# muster_1.net
KiCad netlist of a schematic drawn in EAGLE
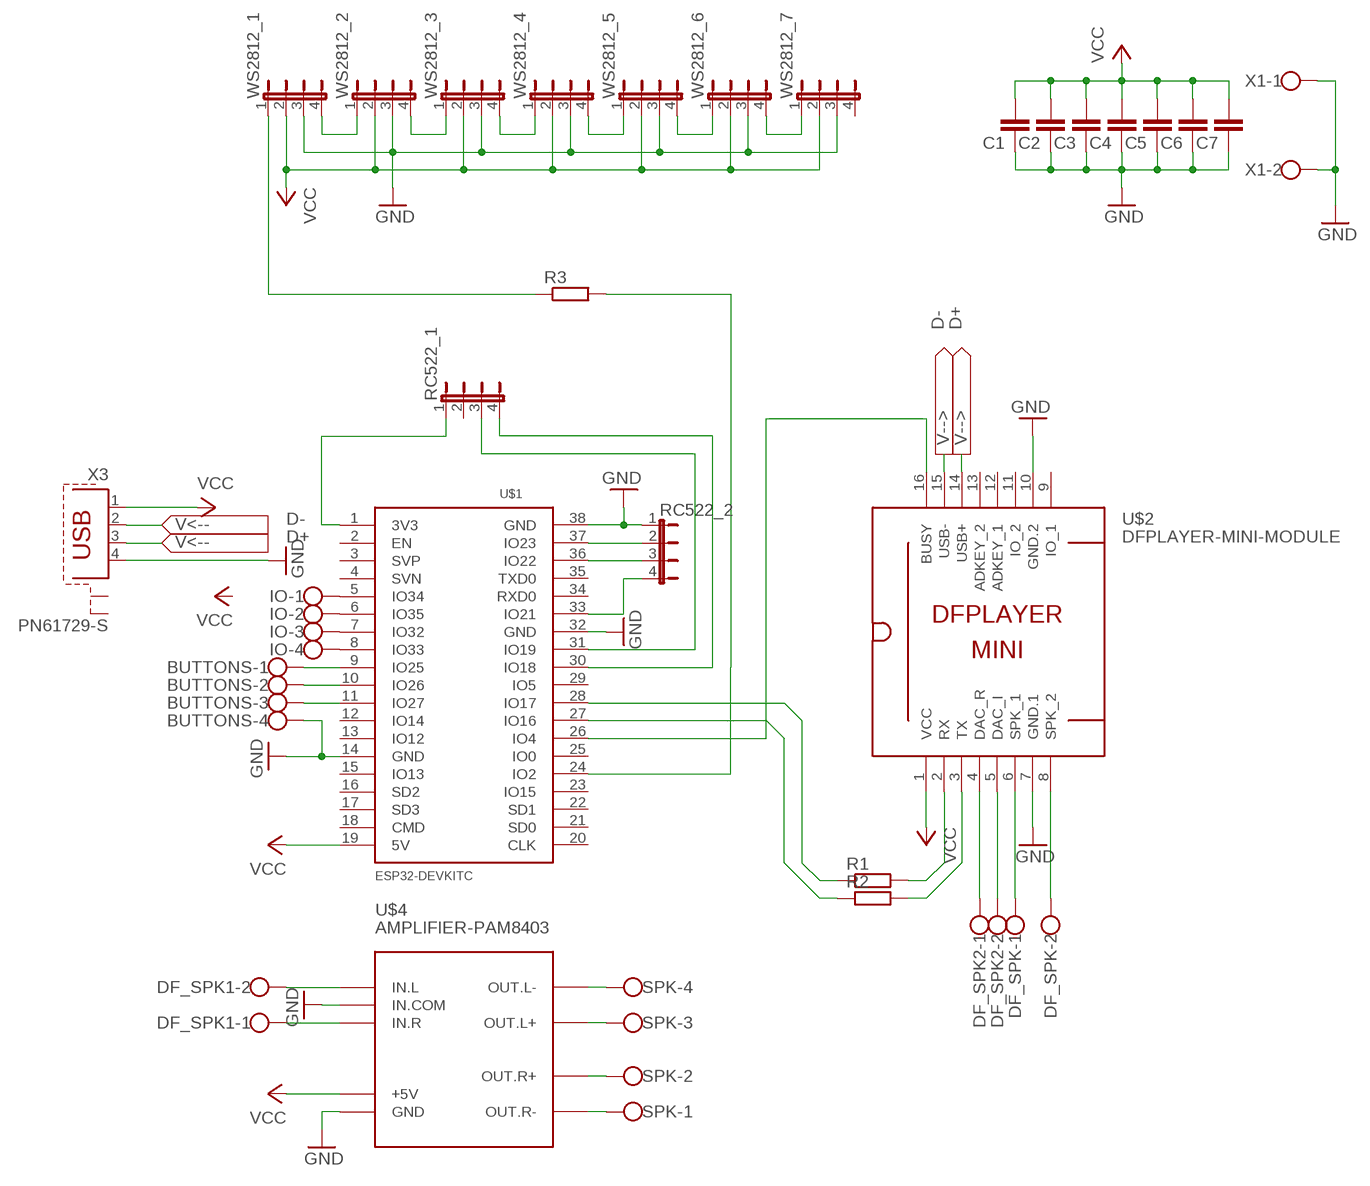
[diagram p0: schematic, sheet 1]

(export (version "E")
  (design (tool "Eeschema 10.0.6"))
  (components
    (comp (ref "BUTTONS")
      (value "W237-4")
      (footprint "eagle-import:W237-4")
      (libsource (lib "eagle-import") (part "W237-4"))
    )
    (comp (ref "C1")
      (value "C-EU025-024X044")
      (footprint "eagle-import:C025-024X044")
      (libsource (lib "eagle-import") (part "C-EU025-024X044"))
    )
    (comp (ref "C2")
      (value "C-EU025-025X050")
      (footprint "eagle-import:C025-025X050")
      (libsource (lib "eagle-import") (part "C-EU025-025X050"))
    )
    (comp (ref "C3")
      (value "C-EU025-025X050")
      (footprint "eagle-import:C025-025X050")
      (libsource (lib "eagle-import") (part "C-EU025-025X050"))
    )
    (comp (ref "C4")
      (value "C-EU025-025X050")
      (footprint "eagle-import:C025-025X050")
      (libsource (lib "eagle-import") (part "C-EU025-025X050"))
    )
    (comp (ref "C5")
      (value "C-EU025-025X050")
      (footprint "eagle-import:C025-025X050")
      (libsource (lib "eagle-import") (part "C-EU025-025X050"))
    )
    (comp (ref "C6")
      (value "C-EU025-025X050")
      (footprint "eagle-import:C025-025X050")
      (libsource (lib "eagle-import") (part "C-EU025-025X050"))
    )
    (comp (ref "C7")
      (value "C-EU025-025X050")
      (footprint "eagle-import:C025-025X050")
      (libsource (lib "eagle-import") (part "C-EU025-025X050"))
    )
    (comp (ref "DF_SPK")
      (value "W237-02P")
      (footprint "eagle-import:W237-132")
      (libsource (lib "eagle-import") (part "W237-02P"))
    )
    (comp (ref "DF_SPK1")
      (value "W237-02P")
      (footprint "eagle-import:W237-132")
      (libsource (lib "eagle-import") (part "W237-02P"))
    )
    (comp (ref "DF_SPK2")
      (value "W237-02P")
      (footprint "eagle-import:W237-132")
      (libsource (lib "eagle-import") (part "W237-02P"))
    )
    (comp (ref "IO")
      (value "W237-4")
      (footprint "eagle-import:W237-4")
      (libsource (lib "eagle-import") (part "W237-4"))
    )
    (comp (ref "R1")
      (value "R-EU_0204/2V")
      (footprint "eagle-import:0204V")
      (libsource (lib "eagle-import") (part "R-EU_0204/2V"))
    )
    (comp (ref "R2")
      (value "R-EU_0204/2V")
      (footprint "eagle-import:0204V")
      (libsource (lib "eagle-import") (part "R-EU_0204/2V"))
    )
    (comp (ref "R3")
      (value "R-EU_0204/2V")
      (footprint "eagle-import:0204V")
      (libsource (lib "eagle-import") (part "R-EU_0204/2V"))
    )
    (comp (ref "RC522_1")
      (value "JP4E")
      (footprint "eagle-import:JP4")
      (libsource (lib "eagle-import") (part "JP4E"))
    )
    (comp (ref "RC522_2")
      (value "JP4E")
      (footprint "eagle-import:JP4")
      (libsource (lib "eagle-import") (part "JP4E"))
    )
    (comp (ref "SPK")
      (value "W237-4")
      (footprint "eagle-import:W237-4")
      (libsource (lib "eagle-import") (part "W237-4"))
    )
    (comp (ref "U$1")
      (value "ESP32DEVKITC")
      (footprint "eagle-import:ESP32-DEVKITC")
      (libsource (lib "eagle-import") (part "ESP32DEVKITC"))
    )
    (comp (ref "U$2")
      (value "DFPLAYER-MINI-MODULE")
      (footprint "eagle-import:DFPLAYER-MINI-MODULE")
      (libsource (lib "eagle-import") (part "DFPLAYER-MINI-MODULE"))
    )
    (comp (ref "U$4")
      (value "AMPLIFIER-PAM8403")
      (footprint "eagle-import:AMPLIFIER-PAM8403")
      (libsource (lib "eagle-import") (part "AMPLIFIER-PAM8403"))
    )
    (comp (ref "WS2812_1")
      (value "JP4E")
      (footprint "eagle-import:JP4")
      (libsource (lib "eagle-import") (part "JP4E"))
    )
    (comp (ref "WS2812_2")
      (value "JP4E")
      (footprint "eagle-import:JP4")
      (libsource (lib "eagle-import") (part "JP4E"))
    )
    (comp (ref "WS2812_3")
      (value "JP4E")
      (footprint "eagle-import:JP4")
      (libsource (lib "eagle-import") (part "JP4E"))
    )
    (comp (ref "WS2812_4")
      (value "JP4E")
      (footprint "eagle-import:JP4")
      (libsource (lib "eagle-import") (part "JP4E"))
    )
    (comp (ref "WS2812_5")
      (value "JP4E")
      (footprint "eagle-import:JP4")
      (libsource (lib "eagle-import") (part "JP4E"))
    )
    (comp (ref "WS2812_6")
      (value "JP4E")
      (footprint "eagle-import:JP4")
      (libsource (lib "eagle-import") (part "JP4E"))
    )
    (comp (ref "WS2812_7")
      (value "JP4E")
      (footprint "eagle-import:JP4")
      (libsource (lib "eagle-import") (part "JP4E"))
    )
    (comp (ref "X1")
      (value "W237-102")
      (footprint "eagle-import:W237-102")
      (libsource (lib "eagle-import") (part "W237-102"))
    )
    (comp (ref "X3")
      (value "PN61729-S")
      (footprint "eagle-import:PN61729-S")
      (libsource (lib "eagle-import") (part "PN61729-S"))
    )
  )
  (nets
    (net (code "1") (name "/D+") (class "Default")
      (node (ref "U$2") (pin "14") (pinfunction "USB+_14") (pintype "bidirectional"))
      (node (ref "X3") (pin "3") (pinfunction "3_3") (pintype "passive"))
    )
    (net (code "2") (name "/D-") (class "Default")
      (node (ref "U$2") (pin "15") (pinfunction "USB-_15") (pintype "bidirectional"))
      (node (ref "X3") (pin "2") (pinfunction "2_2") (pintype "passive"))
    )
    (net (code "3") (name "GND") (class "Default")
      (node (ref "BUTTONS") (pin "4") (pinfunction "KL_4") (pintype "passive"))
      (node (ref "C1") (pin "1") (pinfunction "1_1") (pintype "passive"))
      (node (ref "C2") (pin "1") (pinfunction "1_1") (pintype "passive"))
      (node (ref "C3") (pin "1") (pinfunction "1_1") (pintype "passive"))
      (node (ref "C4") (pin "1") (pinfunction "1_1") (pintype "passive"))
      (node (ref "C5") (pin "1") (pinfunction "1_1") (pintype "passive"))
      (node (ref "C6") (pin "1") (pinfunction "1_1") (pintype "passive"))
      (node (ref "C7") (pin "1") (pinfunction "1_1") (pintype "passive"))
      (node (ref "RC522_2") (pin "1") (pinfunction "1_1") (pintype "passive"))
      (node (ref "U$1") (pin "14") (pinfunction "GND_14") (pintype "bidirectional"))
      (node (ref "U$1") (pin "32") (pinfunction "GND_32") (pintype "bidirectional"))
      (node (ref "U$1") (pin "38") (pinfunction "GND_38") (pintype "bidirectional"))
      (node (ref "U$2") (pin "10") (pinfunction "GND.2_10") (pintype "power_in"))
      (node (ref "U$2") (pin "7") (pinfunction "GND.1_7") (pintype "power_in"))
      (node (ref "U$4") (pin "GND") (pinfunction "GND_GND") (pintype "power_in"))
      (node (ref "U$4") (pin "IN.COM") (pinfunction "IN.COM_IN.COM") (pintype "input"))
      (node (ref "WS2812_1") (pin "3") (pinfunction "3_3") (pintype "passive"))
      (node (ref "WS2812_2") (pin "3") (pinfunction "3_3") (pintype "passive"))
      (node (ref "WS2812_3") (pin "3") (pinfunction "3_3") (pintype "passive"))
      (node (ref "WS2812_4") (pin "3") (pinfunction "3_3") (pintype "passive"))
      (node (ref "WS2812_5") (pin "3") (pinfunction "3_3") (pintype "passive"))
      (node (ref "WS2812_6") (pin "3") (pinfunction "3_3") (pintype "passive"))
      (node (ref "WS2812_7") (pin "3") (pinfunction "3_3") (pintype "passive"))
      (node (ref "X1") (pin "1") (pinfunction "KL_1") (pintype "passive"))
      (node (ref "X1") (pin "2") (pinfunction "KL_2") (pintype "passive"))
      (node (ref "X3") (pin "4") (pinfunction "4_4") (pintype "passive"))
    )
    (net (code "4") (name "Net-(BUTTONSA-KL)") (class "Default")
      (node (ref "BUTTONS") (pin "1") (pinfunction "KL_1") (pintype "passive"))
      (node (ref "U$1") (pin "9") (pinfunction "IO25_9") (pintype "bidirectional"))
    )
    (net (code "5") (name "Net-(BUTTONSB-KL)") (class "Default")
      (node (ref "BUTTONS") (pin "2") (pinfunction "KL_2") (pintype "passive"))
      (node (ref "U$1") (pin "10") (pinfunction "IO26_10") (pintype "bidirectional"))
    )
    (net (code "6") (name "Net-(BUTTONSC-KL)") (class "Default")
      (node (ref "BUTTONS") (pin "3") (pinfunction "KL_3") (pintype "passive"))
      (node (ref "U$1") (pin "11") (pinfunction "IO27_11") (pintype "bidirectional"))
    )
    (net (code "7") (name "Net-(DF_SPK1A-KL)") (class "Default")
      (node (ref "DF_SPK1") (pin "1") (pinfunction "KL_1") (pintype "passive"))
      (node (ref "U$4") (pin "IN.R") (pinfunction "IN.R_IN.R") (pintype "bidirectional"))
    )
    (net (code "8") (name "Net-(DF_SPK1B-KL)") (class "Default")
      (node (ref "DF_SPK1") (pin "2") (pinfunction "KL_2") (pintype "passive"))
      (node (ref "U$4") (pin "IN.L") (pinfunction "IN.L_IN.L") (pintype "input"))
    )
    (net (code "9") (name "Net-(DF_SPK2A-KL)") (class "Default")
      (node (ref "DF_SPK2") (pin "1") (pinfunction "KL_1") (pintype "passive"))
      (node (ref "U$2") (pin "4") (pinfunction "DAC_R_4") (pintype "bidirectional"))
    )
    (net (code "10") (name "Net-(DF_SPK2B-KL)") (class "Default")
      (node (ref "DF_SPK2") (pin "2") (pinfunction "KL_2") (pintype "passive"))
      (node (ref "U$2") (pin "5") (pinfunction "DAC_I_5") (pintype "bidirectional"))
    )
    (net (code "11") (name "Net-(DF_SPKA-KL)") (class "Default")
      (node (ref "DF_SPK") (pin "1") (pinfunction "KL_1") (pintype "passive"))
      (node (ref "U$2") (pin "6") (pinfunction "SPK_1_6") (pintype "bidirectional"))
    )
    (net (code "12") (name "Net-(DF_SPKB-KL)") (class "Default")
      (node (ref "DF_SPK") (pin "2") (pinfunction "KL_2") (pintype "passive"))
      (node (ref "U$2") (pin "8") (pinfunction "SPK_2_8") (pintype "bidirectional"))
    )
    (net (code "13") (name "Net-(IOA-KL)") (class "Default")
      (node (ref "IO") (pin "1") (pinfunction "KL_1") (pintype "passive"))
      (node (ref "U$1") (pin "5") (pinfunction "IO34_5") (pintype "bidirectional"))
    )
    (net (code "14") (name "Net-(IOB-KL)") (class "Default")
      (node (ref "IO") (pin "2") (pinfunction "KL_2") (pintype "passive"))
      (node (ref "U$1") (pin "6") (pinfunction "IO35_6") (pintype "bidirectional"))
    )
    (net (code "15") (name "Net-(IOC-KL)") (class "Default")
      (node (ref "IO") (pin "3") (pinfunction "KL_3") (pintype "passive"))
      (node (ref "U$1") (pin "7") (pinfunction "IO32_7") (pintype "bidirectional"))
    )
    (net (code "16") (name "Net-(IOD-KL)") (class "Default")
      (node (ref "IO") (pin "4") (pinfunction "KL_4") (pintype "passive"))
      (node (ref "U$1") (pin "8") (pinfunction "IO33_8") (pintype "bidirectional"))
    )
    (net (code "17") (name "Net-(R3-Pad1)") (class "Default")
      (node (ref "R3") (pin "1") (pinfunction "1_1") (pintype "passive"))
      (node (ref "WS2812_1") (pin "1") (pinfunction "1_1") (pintype "passive"))
    )
    (net (code "18") (name "Net-(SPKA-KL)") (class "Default")
      (node (ref "SPK") (pin "1") (pinfunction "KL_1") (pintype "passive"))
      (node (ref "U$4") (pin "OUT.R-") (pinfunction "OUT.R-_OUT.R-") (pintype "output"))
    )
    (net (code "19") (name "Net-(SPKB-KL)") (class "Default")
      (node (ref "SPK") (pin "2") (pinfunction "KL_2") (pintype "passive"))
      (node (ref "U$4") (pin "OUT.R+") (pinfunction "OUT.R+_OUT.R+") (pintype "output"))
    )
    (net (code "20") (name "Net-(SPKC-KL)") (class "Default")
      (node (ref "SPK") (pin "3") (pinfunction "KL_3") (pintype "passive"))
      (node (ref "U$4") (pin "OUT.L+") (pinfunction "OUT.L+_OUT.L+") (pintype "output"))
    )
    (net (code "21") (name "Net-(SPKD-KL)") (class "Default")
      (node (ref "SPK") (pin "4") (pinfunction "KL_4") (pintype "passive"))
      (node (ref "U$4") (pin "OUT.L-") (pinfunction "OUT.L-_OUT.L-") (pintype "output"))
    )
    (net (code "22") (name "Net-(U$1-3V3)") (class "Default")
      (node (ref "RC522_1") (pin "1") (pinfunction "1_1") (pintype "passive"))
      (node (ref "U$1") (pin "1") (pinfunction "3V3_1") (pintype "bidirectional"))
    )
    (net (code "23") (name "Net-(U$1-IO2)") (class "Default")
      (node (ref "R3") (pin "2") (pinfunction "2_2") (pintype "passive"))
      (node (ref "U$1") (pin "24") (pinfunction "IO2_24") (pintype "bidirectional"))
    )
    (net (code "24") (name "Net-(U$1-IO4)") (class "Default")
      (node (ref "U$1") (pin "26") (pinfunction "IO4_26") (pintype "bidirectional"))
      (node (ref "U$2") (pin "16") (pinfunction "BUSY_16") (pintype "bidirectional"))
    )
    (net (code "25") (name "Net-(U$1-IO16)") (class "Default")
      (node (ref "R2") (pin "1") (pinfunction "1_1") (pintype "passive"))
      (node (ref "U$1") (pin "27") (pinfunction "IO16_27") (pintype "bidirectional"))
    )
    (net (code "26") (name "Net-(U$1-IO17)") (class "Default")
      (node (ref "R1") (pin "1") (pinfunction "1_1") (pintype "passive"))
      (node (ref "U$1") (pin "28") (pinfunction "IO17_28") (pintype "bidirectional"))
    )
    (net (code "27") (name "Net-(U$1-IO18)") (class "Default")
      (node (ref "RC522_1") (pin "4") (pinfunction "4_4") (pintype "passive"))
      (node (ref "U$1") (pin "30") (pinfunction "IO18_30") (pintype "bidirectional"))
    )
    (net (code "28") (name "Net-(U$1-IO19)") (class "Default")
      (node (ref "RC522_1") (pin "3") (pinfunction "3_3") (pintype "passive"))
      (node (ref "U$1") (pin "31") (pinfunction "IO19_31") (pintype "bidirectional"))
    )
    (net (code "29") (name "Net-(U$1-IO21)") (class "Default")
      (node (ref "RC522_2") (pin "4") (pinfunction "4_4") (pintype "passive"))
      (node (ref "U$1") (pin "33") (pinfunction "IO21_33") (pintype "bidirectional"))
    )
    (net (code "30") (name "Net-(U$1-IO22)") (class "Default")
      (node (ref "RC522_2") (pin "3") (pinfunction "3_3") (pintype "passive"))
      (node (ref "U$1") (pin "36") (pinfunction "IO22_36") (pintype "bidirectional"))
    )
    (net (code "31") (name "Net-(U$1-IO23)") (class "Default")
      (node (ref "RC522_2") (pin "2") (pinfunction "2_2") (pintype "passive"))
      (node (ref "U$1") (pin "37") (pinfunction "IO23_37") (pintype "bidirectional"))
    )
    (net (code "32") (name "Net-(U$2-RX)") (class "Default")
      (node (ref "R1") (pin "2") (pinfunction "2_2") (pintype "passive"))
      (node (ref "U$2") (pin "2") (pinfunction "RX_2") (pintype "bidirectional"))
    )
    (net (code "33") (name "Net-(U$2-TX)") (class "Default")
      (node (ref "R2") (pin "2") (pinfunction "2_2") (pintype "passive"))
      (node (ref "U$2") (pin "3") (pinfunction "TX_3") (pintype "bidirectional"))
    )
    (net (code "34") (name "Net-(WS2812_1-Pad4)") (class "Default")
      (node (ref "WS2812_1") (pin "4") (pinfunction "4_4") (pintype "passive"))
      (node (ref "WS2812_2") (pin "1") (pinfunction "1_1") (pintype "passive"))
    )
    (net (code "35") (name "Net-(WS2812_2-Pad4)") (class "Default")
      (node (ref "WS2812_2") (pin "4") (pinfunction "4_4") (pintype "passive"))
      (node (ref "WS2812_3") (pin "1") (pinfunction "1_1") (pintype "passive"))
    )
    (net (code "36") (name "Net-(WS2812_3-Pad4)") (class "Default")
      (node (ref "WS2812_3") (pin "4") (pinfunction "4_4") (pintype "passive"))
      (node (ref "WS2812_4") (pin "1") (pinfunction "1_1") (pintype "passive"))
    )
    (net (code "37") (name "Net-(WS2812_4-Pad4)") (class "Default")
      (node (ref "WS2812_4") (pin "4") (pinfunction "4_4") (pintype "passive"))
      (node (ref "WS2812_5") (pin "1") (pinfunction "1_1") (pintype "passive"))
    )
    (net (code "38") (name "Net-(WS2812_5-Pad4)") (class "Default")
      (node (ref "WS2812_5") (pin "4") (pinfunction "4_4") (pintype "passive"))
      (node (ref "WS2812_6") (pin "1") (pinfunction "1_1") (pintype "passive"))
    )
    (net (code "39") (name "Net-(WS2812_6-Pad4)") (class "Default")
      (node (ref "WS2812_6") (pin "4") (pinfunction "4_4") (pintype "passive"))
      (node (ref "WS2812_7") (pin "1") (pinfunction "1_1") (pintype "passive"))
    )
    (net (code "40") (name "VCC") (class "Default")
      (node (ref "C1") (pin "2") (pinfunction "2_2") (pintype "passive"))
      (node (ref "C2") (pin "2") (pinfunction "2_2") (pintype "passive"))
      (node (ref "C3") (pin "2") (pinfunction "2_2") (pintype "passive"))
      (node (ref "C4") (pin "2") (pinfunction "2_2") (pintype "passive"))
      (node (ref "C5") (pin "2") (pinfunction "2_2") (pintype "passive"))
      (node (ref "C6") (pin "2") (pinfunction "2_2") (pintype "passive"))
      (node (ref "C7") (pin "2") (pinfunction "2_2") (pintype "passive"))
      (node (ref "U$1") (pin "19") (pinfunction "5V_19") (pintype "bidirectional"))
      (node (ref "U$2") (pin "1") (pinfunction "VCC_1") (pintype "power_in"))
      (node (ref "U$4") (pin "+5V") (pinfunction "+5V_+5V") (pintype "power_in"))
      (node (ref "WS2812_1") (pin "2") (pinfunction "2_2") (pintype "passive"))
      (node (ref "WS2812_2") (pin "2") (pinfunction "2_2") (pintype "passive"))
      (node (ref "WS2812_3") (pin "2") (pinfunction "2_2") (pintype "passive"))
      (node (ref "WS2812_4") (pin "2") (pinfunction "2_2") (pintype "passive"))
      (node (ref "WS2812_5") (pin "2") (pinfunction "2_2") (pintype "passive"))
      (node (ref "WS2812_6") (pin "2") (pinfunction "2_2") (pintype "passive"))
      (node (ref "WS2812_7") (pin "2") (pinfunction "2_2") (pintype "passive"))
      (node (ref "X3") (pin "1") (pinfunction "1_1") (pintype "passive"))
    )
    (net (code "41") (name "unconnected-(RC522_1-Pad2)") (class "Default")
      (node (ref "RC522_1") (pin "2") (pinfunction "2_2") (pintype "passive"))
    )
    (net (code "42") (name "unconnected-(U$1-CLK-Pad20)") (class "Default")
      (node (ref "U$1") (pin "20") (pinfunction "CLK_20") (pintype "bidirectional"))
    )
    (net (code "43") (name "unconnected-(U$1-CMD-Pad18)") (class "Default")
      (node (ref "U$1") (pin "18") (pinfunction "CMD_18") (pintype "bidirectional"))
    )
    (net (code "44") (name "unconnected-(U$1-EN-Pad2)") (class "Default")
      (node (ref "U$1") (pin "2") (pinfunction "EN_2") (pintype "bidirectional"))
    )
    (net (code "45") (name "unconnected-(U$1-IO0-Pad25)") (class "Default")
      (node (ref "U$1") (pin "25") (pinfunction "IO0_25") (pintype "bidirectional"))
    )
    (net (code "46") (name "unconnected-(U$1-IO5-Pad29)") (class "Default")
      (node (ref "U$1") (pin "29") (pinfunction "IO5_29") (pintype "bidirectional"))
    )
    (net (code "47") (name "unconnected-(U$1-IO12-Pad13)") (class "Default")
      (node (ref "U$1") (pin "13") (pinfunction "IO12_13") (pintype "bidirectional"))
    )
    (net (code "48") (name "unconnected-(U$1-IO13-Pad15)") (class "Default")
      (node (ref "U$1") (pin "15") (pinfunction "IO13_15") (pintype "bidirectional"))
    )
    (net (code "49") (name "unconnected-(U$1-IO14-Pad12)") (class "Default")
      (node (ref "U$1") (pin "12") (pinfunction "IO14_12") (pintype "bidirectional"))
    )
    (net (code "50") (name "unconnected-(U$1-IO15-Pad23)") (class "Default")
      (node (ref "U$1") (pin "23") (pinfunction "IO15_23") (pintype "bidirectional"))
    )
    (net (code "51") (name "unconnected-(U$1-RXD0-Pad34)") (class "Default")
      (node (ref "U$1") (pin "34") (pinfunction "RXD0_34") (pintype "bidirectional"))
    )
    (net (code "52") (name "unconnected-(U$1-SD0-Pad21)") (class "Default")
      (node (ref "U$1") (pin "21") (pinfunction "SD0_21") (pintype "bidirectional"))
    )
    (net (code "53") (name "unconnected-(U$1-SD1-Pad22)") (class "Default")
      (node (ref "U$1") (pin "22") (pinfunction "SD1_22") (pintype "bidirectional"))
    )
    (net (code "54") (name "unconnected-(U$1-SD2-Pad16)") (class "Default")
      (node (ref "U$1") (pin "16") (pinfunction "SD2_16") (pintype "bidirectional"))
    )
    (net (code "55") (name "unconnected-(U$1-SD3-Pad17)") (class "Default")
      (node (ref "U$1") (pin "17") (pinfunction "SD3_17") (pintype "bidirectional"))
    )
    (net (code "56") (name "unconnected-(U$1-SVN-Pad4)") (class "Default")
      (node (ref "U$1") (pin "4") (pinfunction "SVN_4") (pintype "bidirectional"))
    )
    (net (code "57") (name "unconnected-(U$1-SVP-Pad3)") (class "Default")
      (node (ref "U$1") (pin "3") (pinfunction "SVP_3") (pintype "bidirectional"))
    )
    (net (code "58") (name "unconnected-(U$1-TXD0-Pad35)") (class "Default")
      (node (ref "U$1") (pin "35") (pinfunction "TXD0_35") (pintype "bidirectional"))
    )
    (net (code "59") (name "unconnected-(U$2-ADKEY_1-Pad12)") (class "Default")
      (node (ref "U$2") (pin "12") (pinfunction "ADKEY_1_12") (pintype "bidirectional"))
    )
    (net (code "60") (name "unconnected-(U$2-ADKEY_2-Pad13)") (class "Default")
      (node (ref "U$2") (pin "13") (pinfunction "ADKEY_2_13") (pintype "bidirectional"))
    )
    (net (code "61") (name "unconnected-(U$2-IO_1-Pad9)") (class "Default")
      (node (ref "U$2") (pin "9") (pinfunction "IO_1_9") (pintype "bidirectional"))
    )
    (net (code "62") (name "unconnected-(U$2-IO_2-Pad11)") (class "Default")
      (node (ref "U$2") (pin "11") (pinfunction "IO_2_11") (pintype "bidirectional"))
    )
    (net (code "63") (name "unconnected-(WS2812_7-Pad4)") (class "Default")
      (node (ref "WS2812_7") (pin "4") (pinfunction "4_4") (pintype "passive"))
    )
    (net (code "64") (name "unconnected-(X3-PadS1)") (class "Default")
      (node (ref "X3") (pin "S1") (pinfunction "S1_S1") (pintype "passive"))
    )
    (net (code "65") (name "unconnected-(X3-PadS2)") (class "Default")
      (node (ref "X3") (pin "S2") (pinfunction "S2_S2") (pintype "passive"))
    )
  )
)
